# 04b3_BATT_CHARGER.net
KiCad netlist of a schematic drawn in Altium Designer
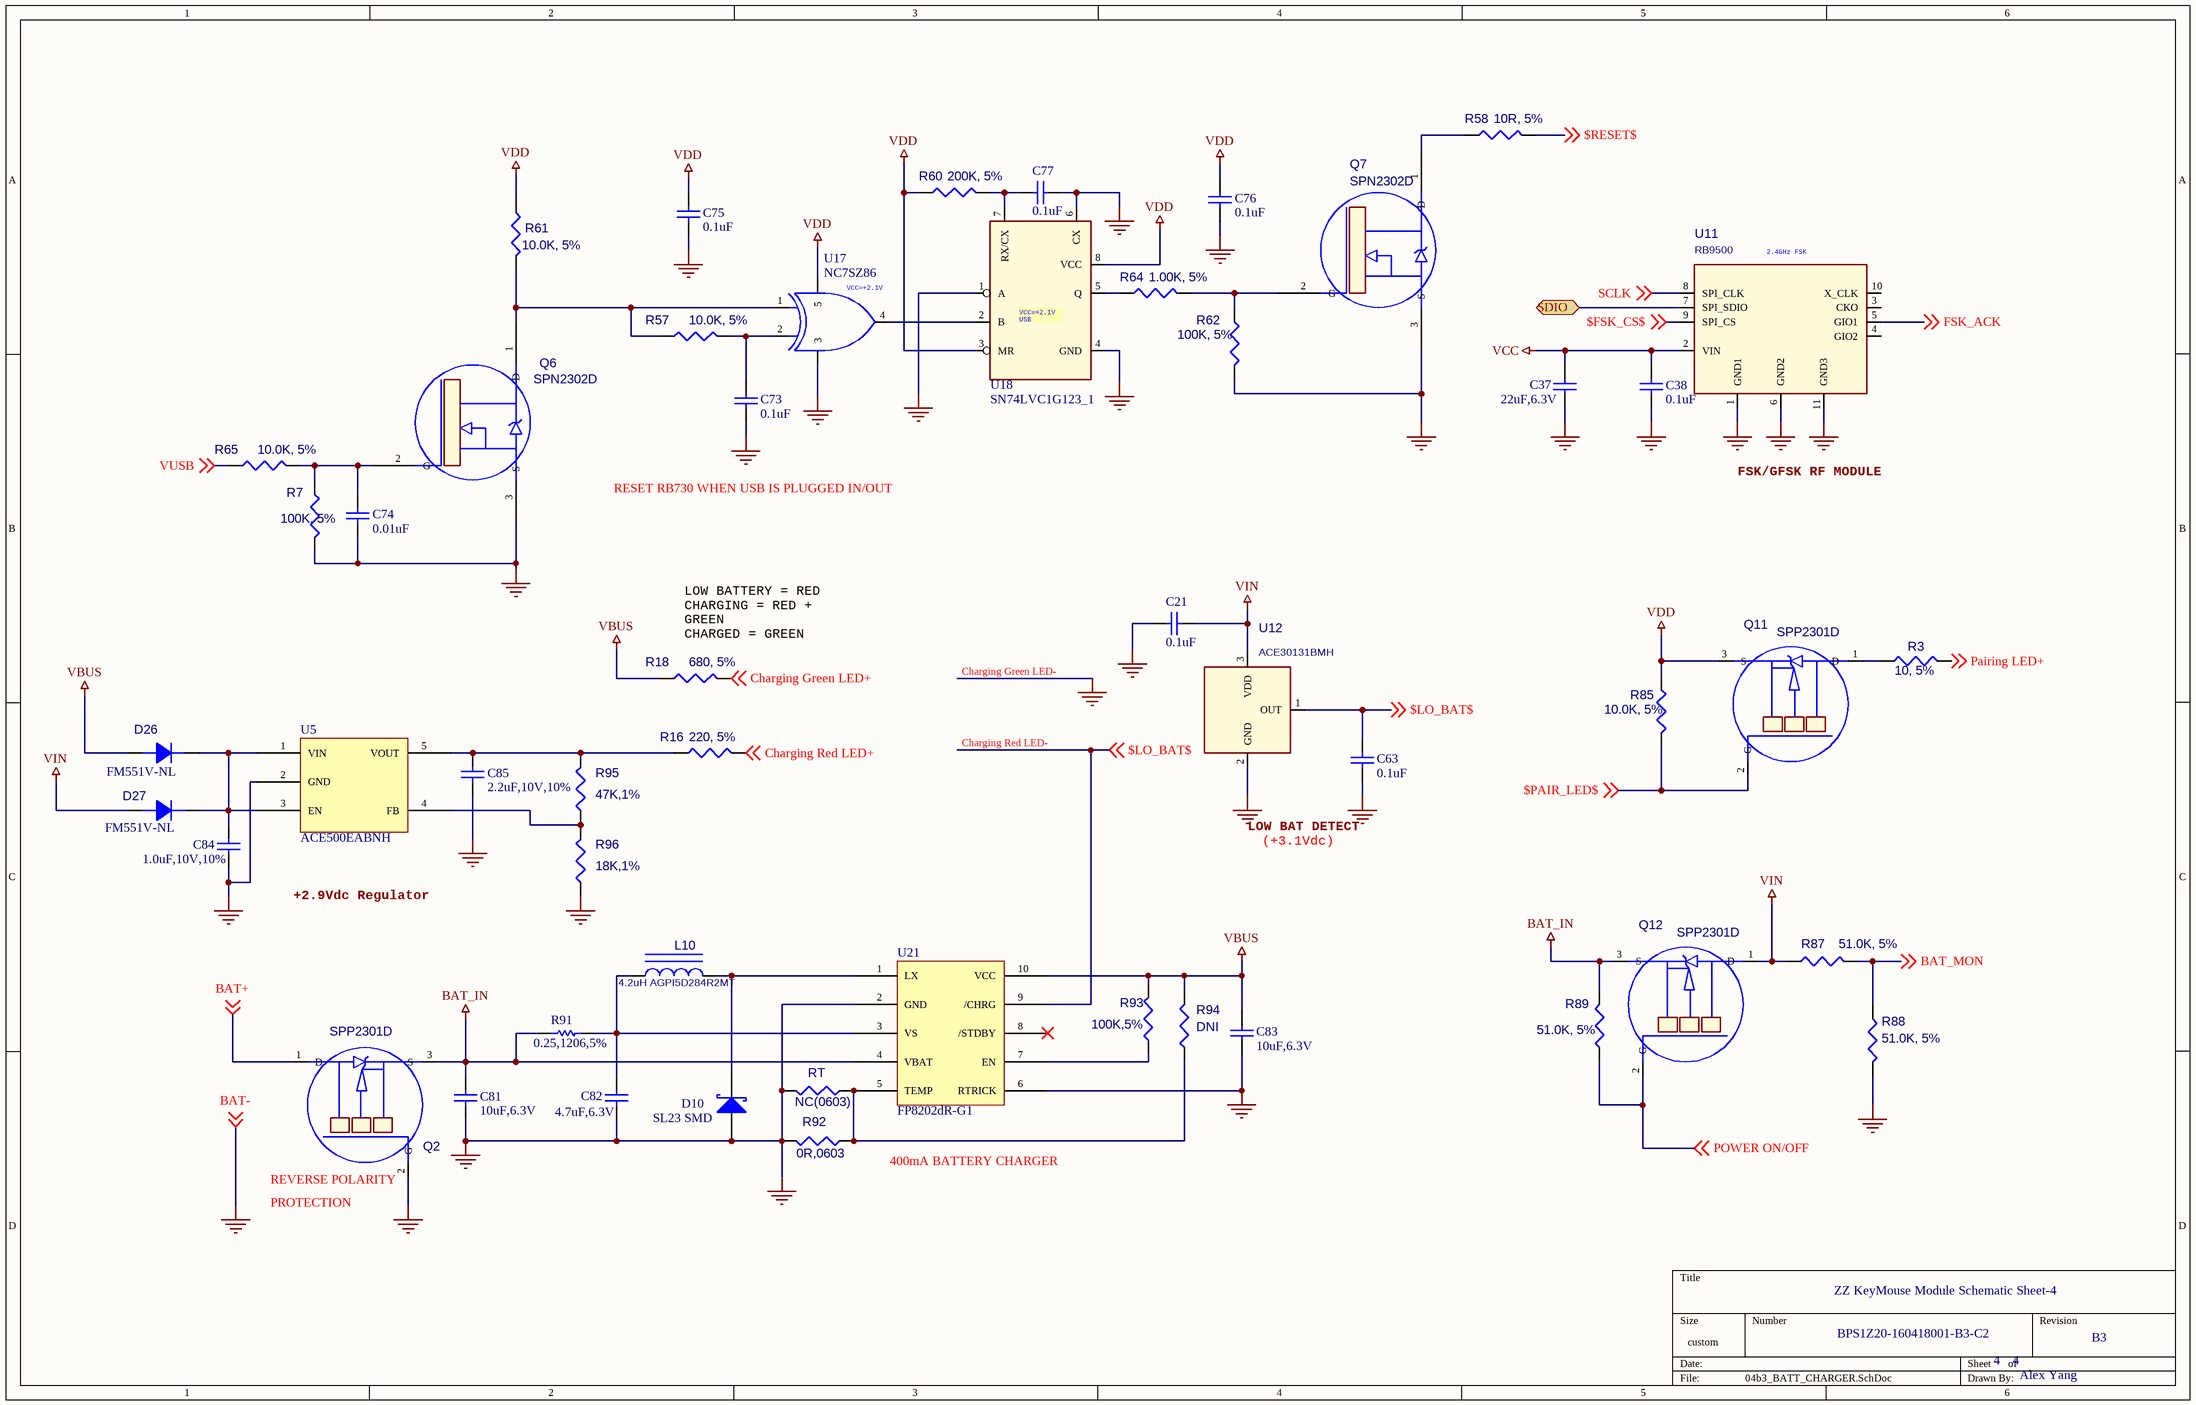
[diagram p0: 04b3_BATT_CHARGER.SchDoc]

(export (version "E")
  (design (tool "Eeschema 10.0.6"))
  (components
    (comp (ref "C21")
      (value "0.1uF")
      (footprint "0603")
      (description "Capacitor")
      (libsource (lib "Miscellaneous Devices") (part "Cap"))
    )
    (comp (ref "C37")
      (value "22uF,6.3V")
      (footprint "MIN0805")
      (description "Capacitor")
      (libsource (lib "Miscellaneous Devices") (part "Cap"))
    )
    (comp (ref "C38")
      (value "0.1uF")
      (footprint "0603")
      (description "Capacitor")
      (libsource (lib "Miscellaneous Devices") (part "Cap"))
    )
    (comp (ref "C63")
      (value "0.1uF")
      (footprint "0603")
      (description "Capacitor")
      (libsource (lib "Miscellaneous Devices") (part "Cap"))
    )
    (comp (ref "C73")
      (value "0.1uF")
      (footprint "0603")
      (description "Capacitor")
      (libsource (lib "Miscellaneous Devices") (part "Cap"))
    )
    (comp (ref "C74")
      (value "0.01uF")
      (footprint "0603")
      (description "Capacitor")
      (libsource (lib "Miscellaneous Devices") (part "Cap"))
    )
    (comp (ref "C75")
      (value "0.1uF")
      (footprint "0603")
      (description "Capacitor")
      (libsource (lib "Miscellaneous Devices") (part "Cap"))
    )
    (comp (ref "C76")
      (value "0.1uF")
      (footprint "0603")
      (description "Capacitor")
      (libsource (lib "Miscellaneous Devices") (part "Cap"))
    )
    (comp (ref "C77")
      (value "0.1uF")
      (footprint "0603")
      (description "Capacitor")
      (libsource (lib "Miscellaneous Devices") (part "Cap"))
    )
    (comp (ref "C81")
      (value "10uF,6.3V")
      (footprint "0603")
      (description "Capacitor")
      (libsource (lib "Miscellaneous Devices") (part "Cap"))
    )
    (comp (ref "C82")
      (value "4.7uF,6.3V")
      (footprint "0603")
      (description "Capacitor")
      (libsource (lib "Miscellaneous Devices") (part "Cap"))
    )
    (comp (ref "C83")
      (value "10uF,6.3V")
      (footprint "0603")
      (description "Capacitor")
      (libsource (lib "Miscellaneous Devices") (part "Cap"))
    )
    (comp (ref "C84")
      (value "1.0uF,10V,10%")
      (footprint "0603")
      (description "Capacitor")
      (libsource (lib "Miscellaneous Devices") (part "Cap"))
    )
    (comp (ref "C85")
      (value "2.2uF,10V,10%")
      (footprint "0603")
      (description "Capacitor")
      (libsource (lib "Miscellaneous Devices") (part "Cap"))
    )
    (comp (ref "D10")
      (value "SL23 SMD")
      (footprint "Sl23")
      (description "Silicon RF Schottky")
      (fields (field (name "PUBLISHER") "Altium Limited"))
      (libsource (lib "Miscellaneous Devices") (part "Diode BAT17"))
    )
    (comp (ref "D26")
      (value "DIODE")
      (footprint "FM551-NL-2")
      (fields (field (name "ALTIUM_UNNAMED_1") "FM551V-NL"))
      (libsource (lib "L MAIN_Library") (part "DIODE"))
    )
    (comp (ref "D27")
      (value "DIODE")
      (footprint "FM551-NL-2")
      (fields (field (name "ALTIUM_UNNAMED_1") "FM551V-NL"))
      (libsource (lib "L MAIN_Library") (part "DIODE"))
    )
    (comp (ref "L10")
      (value "4.2uH AGPI5D284R2MT")
      (footprint "AGPI15D284R2MT")
      (libsource (lib "*") (part "INDUCTOR IRON"))
    )
    (comp (ref "Q2") (value "SPP2301D") (footprint "SOT23") (libsource (lib "") (part "AO3435_1")))
    (comp (ref "Q6") (value "SPN2302D") (footprint "SOT23") (libsource (lib "L MAIN") (part "AO3416")))
    (comp (ref "Q7") (value "SPN2302D") (footprint "SOT23") (libsource (lib "L MAIN") (part "AO3416")))
    (comp (ref "Q11") (value "SPP2301D") (footprint "SOT23") (libsource (lib "R MAIN") (part "AO3435")))
    (comp (ref "Q12") (value "SPP2301D") (footprint "SOT23") (libsource (lib "R MAIN") (part "AO3435")))
    (comp (ref "R3") (value "10, 5%") (footprint "0402") (libsource (lib "*") (part "R")))
    (comp (ref "R7") (value "100K, 5%") (footprint "0402") (libsource (lib "*") (part "R")))
    (comp (ref "R16") (value "220, 5%") (footprint "0402") (libsource (lib "*") (part "R")))
    (comp (ref "R18") (value "680, 5%") (footprint "0402") (libsource (lib "*") (part "R")))
    (comp (ref "R57") (value "10.0K, 5%") (footprint "0402") (libsource (lib "*") (part "R")))
    (comp (ref "R58") (value "10R, 5%") (footprint "0402") (libsource (lib "*") (part "R")))
    (comp (ref "R60") (value "200K, 5%") (footprint "0402") (libsource (lib "*") (part "R")))
    (comp (ref "R61") (value "10.0K, 5%") (footprint "0402") (libsource (lib "*") (part "R")))
    (comp (ref "R62") (value "100K, 5%") (footprint "0402") (libsource (lib "*") (part "R")))
    (comp (ref "R64") (value "1.00K, 5%") (footprint "0402") (libsource (lib "*") (part "R")))
    (comp (ref "R65") (value "10.0K, 5%") (footprint "0402") (libsource (lib "*") (part "R")))
    (comp (ref "R85") (value "10.0K, 5%") (footprint "0402") (libsource (lib "*") (part "R")))
    (comp (ref "R87") (value "51.0K, 5%") (footprint "0402") (libsource (lib "*") (part "R")))
    (comp (ref "R88") (value "51.0K, 5%") (footprint "0402") (libsource (lib "*") (part "R")))
    (comp (ref "R89") (value "51.0K, 5%") (footprint "0402") (libsource (lib "*") (part "R")))
    (comp (ref "R91")
      (value "0.25,1206,5%")
      (footprint "1206")
      (description "Resistor")
      (fields (field (name "PUBLISHER") "Altium Limited"))
      (libsource (lib "Miscellaneous Devices") (part "Res1"))
    )
    (comp (ref "R92") (value "0R,0603") (footprint "0603") (libsource (lib "*") (part "R")))
    (comp (ref "R93") (value "100K,5%") (footprint "0402") (libsource (lib "*") (part "R")))
    (comp (ref "R94") (value "DNI") (footprint "0402") (libsource (lib "*") (part "R")))
    (comp (ref "R95") (value "47K,1%") (footprint "0402") (libsource (lib "*") (part "R")))
    (comp (ref "R96") (value "18K,1%") (footprint "0402") (libsource (lib "*") (part "R")))
    (comp (ref "RT") (value "NC(0603)") (footprint "0603") (libsource (lib "*") (part "R")))
    (comp (ref "U5")
      (value "ACE500EABNH")
      (footprint "SOT23-5")
      (fields (field (name "PUBLISHER") "Altium Limited"))
      (libsource (lib "ZZ KeyMouse Module") (part "ACE500EABNH"))
    )
    (comp (ref "U11") (value "RB9500") (footprint "RB9500_MODULE_SMT") (libsource (lib "*") (part "RB9500")))
    (comp (ref "U12") (value "ACE30131BMH") (footprint "SOT23") (libsource (lib "*") (part "STM1061N31WX6F")))
    (comp (ref "U17")
      (value "NC7SZ86")
      (footprint "SC70-5")
      (libsource (lib "L MAIN_Library") (part "NC7SZ86"))
    )
    (comp (ref "U18")
      (value "SN74LVC1G123_1")
      (footprint "US8_ON_SEMI_2MMX2.3MM")
      (libsource (lib "L MAIN_Library") (part "SN74LVC1G123_1"))
    )
    (comp (ref "U21")
      (value "FP8202dR-G1")
      (footprint "DFN10")
      (fields (field (name "PUBLISHER") "Altium Limited"))
      (libsource (lib "ZZ KeyMouse Module") (part "FP8202dR-G1"))
    )
  )
  (nets
    (net (code "1") (name "$FSK_CS$") (class "Default")
      (node (ref "U11") (pin "9") (pinfunction "SPI_CS_9") (pintype "passive"))
    )
    (net (code "2") (name "$LO_BAT$") (class "Default")
      (node (ref "C63") (pin "2") (pinfunction "2_2") (pintype "passive"))
      (node (ref "U12") (pin "1") (pinfunction "OUT_1") (pintype "passive"))
      (node (ref "U21") (pin "9") (pinfunction "/CHRG_9") (pintype "passive"))
    )
    (net (code "3") (name "$PAIR_LED$") (class "Default")
      (node (ref "Q11") (pin "2") (pinfunction "G_2") (pintype "passive"))
      (node (ref "R85") (pin "2") (pinfunction "2_2") (pintype "passive"))
    )
    (net (code "4") (name "$RESET$") (class "Default")
      (node (ref "R58") (pin "2") (pinfunction "2_2") (pintype "passive"))
    )
    (net (code "5") (name "/SDIO") (class "Default")
      (node (ref "U11") (pin "7") (pinfunction "SPI_SDIO_7") (pintype "passive"))
    )
    (net (code "6") (name "BAT+") (class "Default")
      (node (ref "Q2") (pin "1") (pinfunction "D_1") (pintype "passive"))
    )
    (net (code "7") (name "BAT-") (class "Default")
      (node (ref "C21") (pin "2") (pinfunction "2_2") (pintype "passive"))
      (node (ref "C37") (pin "1") (pinfunction "1_1") (pintype "passive"))
      (node (ref "C38") (pin "1") (pinfunction "1_1") (pintype "passive"))
      (node (ref "C63") (pin "1") (pinfunction "1_1") (pintype "passive"))
      (node (ref "C73") (pin "1") (pinfunction "1_1") (pintype "passive"))
      (node (ref "C74") (pin "1") (pinfunction "1_1") (pintype "passive"))
      (node (ref "C75") (pin "1") (pinfunction "1_1") (pintype "passive"))
      (node (ref "C76") (pin "1") (pinfunction "1_1") (pintype "passive"))
      (node (ref "C77") (pin "1") (pinfunction "1_1") (pintype "passive"))
      (node (ref "C81") (pin "1") (pinfunction "1_1") (pintype "passive"))
      (node (ref "C82") (pin "1") (pinfunction "1_1") (pintype "passive"))
      (node (ref "C83") (pin "1") (pinfunction "1_1") (pintype "passive"))
      (node (ref "C84") (pin "1") (pinfunction "1_1") (pintype "passive"))
      (node (ref "C85") (pin "1") (pinfunction "1_1") (pintype "passive"))
      (node (ref "D10") (pin "1") (pinfunction "A_1") (pintype "passive"))
      (node (ref "Q2") (pin "2") (pinfunction "G_2") (pintype "passive"))
      (node (ref "Q6") (pin "3") (pinfunction "S_3") (pintype "passive"))
      (node (ref "Q7") (pin "3") (pinfunction "S_3") (pintype "passive"))
      (node (ref "R62") (pin "1") (pinfunction "1_1") (pintype "passive"))
      (node (ref "R7") (pin "1") (pinfunction "1_1") (pintype "passive"))
      (node (ref "R88") (pin "2") (pinfunction "2_2") (pintype "passive"))
      (node (ref "R92") (pin "1") (pinfunction "1_1") (pintype "passive"))
      (node (ref "R96") (pin "2") (pinfunction "2_2") (pintype "passive"))
      (node (ref "RT") (pin "1") (pinfunction "1_1") (pintype "passive"))
      (node (ref "U11") (pin "1") (pinfunction "GND1_1") (pintype "passive"))
      (node (ref "U11") (pin "11") (pinfunction "GND3_11") (pintype "passive"))
      (node (ref "U11") (pin "6") (pinfunction "GND2_6") (pintype "passive"))
      (node (ref "U12") (pin "2") (pinfunction "GND_2") (pintype "passive"))
      (node (ref "U17") (pin "3") (pinfunction "3_3") (pintype "power_in"))
      (node (ref "U18") (pin "1") (pinfunction "A_1") (pintype "passive"))
      (node (ref "U18") (pin "4") (pinfunction "GND_4") (pintype "power_in"))
      (node (ref "U18") (pin "6") (pinfunction "CX_6") (pintype "passive"))
      (node (ref "U21") (pin "2") (pinfunction "GND_2") (pintype "passive"))
      (node (ref "U21") (pin "6") (pinfunction "RTRICK_6") (pintype "passive"))
      (node (ref "U5") (pin "2") (pinfunction "GND_2") (pintype "passive"))
    )
    (net (code "8") (name "BAT_IN") (class "Default")
      (node (ref "C81") (pin "2") (pinfunction "2_2") (pintype "passive"))
      (node (ref "Q12") (pin "3") (pinfunction "S_3") (pintype "passive"))
      (node (ref "Q2") (pin "3") (pinfunction "S_3") (pintype "passive"))
      (node (ref "R89") (pin "1") (pinfunction "1_1") (pintype "passive"))
      (node (ref "R91") (pin "1") (pinfunction "1_1") (pintype "passive"))
      (node (ref "U21") (pin "4") (pinfunction "VBAT_4") (pintype "passive"))
    )
    (net (code "9") (name "BAT_MON") (class "Default")
      (node (ref "R87") (pin "2") (pinfunction "2_2") (pintype "passive"))
      (node (ref "R88") (pin "1") (pinfunction "1_1") (pintype "passive"))
    )
    (net (code "10") (name "Charging Green LED+") (class "Default")
      (node (ref "R18") (pin "2") (pinfunction "2_2") (pintype "passive"))
    )
    (net (code "11") (name "Charging Red LED+") (class "Default")
      (node (ref "R16") (pin "2") (pinfunction "2_2") (pintype "passive"))
    )
    (net (code "12") (name "FSK_ACK") (class "Default")
      (node (ref "U11") (pin "5") (pinfunction "GIO1_5") (pintype "passive"))
    )
    (net (code "13") (name "Net-(C73-Pad2)") (class "Default")
      (node (ref "C73") (pin "2") (pinfunction "2_2") (pintype "passive"))
      (node (ref "R57") (pin "2") (pinfunction "2_2") (pintype "passive"))
      (node (ref "U17") (pin "2") (pinfunction "2_2") (pintype "passive"))
    )
    (net (code "14") (name "Net-(D10-K)") (class "Default")
      (node (ref "D10") (pin "2") (pinfunction "K_2") (pintype "passive"))
      (node (ref "L10") (pin "2") (pinfunction "2_2") (pintype "passive"))
      (node (ref "U21") (pin "1") (pinfunction "LX_1") (pintype "passive"))
    )
    (net (code "15") (name "Net-(Q6-D)") (class "Default")
      (node (ref "Q6") (pin "1") (pinfunction "D_1") (pintype "passive"))
      (node (ref "R57") (pin "1") (pinfunction "1_1") (pintype "passive"))
      (node (ref "R61") (pin "2") (pinfunction "2_2") (pintype "passive"))
      (node (ref "U17") (pin "1") (pinfunction "1_1") (pintype "passive"))
    )
    (net (code "16") (name "Net-(Q6-G)") (class "Default")
      (node (ref "C74") (pin "2") (pinfunction "2_2") (pintype "passive"))
      (node (ref "Q6") (pin "2") (pinfunction "G_2") (pintype "passive"))
      (node (ref "R65") (pin "2") (pinfunction "2_2") (pintype "passive"))
      (node (ref "R7") (pin "2") (pinfunction "2_2") (pintype "passive"))
    )
    (net (code "17") (name "Net-(Q7-D)") (class "Default")
      (node (ref "Q7") (pin "1") (pinfunction "D_1") (pintype "passive"))
      (node (ref "R58") (pin "1") (pinfunction "1_1") (pintype "passive"))
    )
    (net (code "18") (name "Net-(Q7-G)") (class "Default")
      (node (ref "Q7") (pin "2") (pinfunction "G_2") (pintype "passive"))
      (node (ref "R62") (pin "2") (pinfunction "2_2") (pintype "passive"))
      (node (ref "R64") (pin "2") (pinfunction "2_2") (pintype "passive"))
    )
    (net (code "19") (name "Net-(Q11-D)") (class "Default")
      (node (ref "Q11") (pin "1") (pinfunction "D_1") (pintype "passive"))
      (node (ref "R3") (pin "1") (pinfunction "1_1") (pintype "passive"))
    )
    (net (code "20") (name "Net-(U5-EN)") (class "Default")
      (node (ref "C84") (pin "2") (pinfunction "2_2") (pintype "passive"))
      (node (ref "D26") (pin "K") (pinfunction "K_K") (pintype "passive"))
      (node (ref "D27") (pin "K") (pinfunction "K_K") (pintype "passive"))
      (node (ref "U5") (pin "1") (pinfunction "VIN_1") (pintype "passive"))
      (node (ref "U5") (pin "3") (pinfunction "EN_3") (pintype "passive"))
    )
    (net (code "21") (name "Net-(U5-FB)") (class "Default")
      (node (ref "R95") (pin "2") (pinfunction "2_2") (pintype "passive"))
      (node (ref "R96") (pin "1") (pinfunction "1_1") (pintype "passive"))
      (node (ref "U5") (pin "4") (pinfunction "FB_4") (pintype "passive"))
    )
    (net (code "22") (name "Net-(U5-VOUT)") (class "Default")
      (node (ref "C85") (pin "2") (pinfunction "2_2") (pintype "passive"))
      (node (ref "R16") (pin "1") (pinfunction "1_1") (pintype "passive"))
      (node (ref "R95") (pin "1") (pinfunction "1_1") (pintype "passive"))
      (node (ref "U5") (pin "5") (pinfunction "VOUT_5") (pintype "passive"))
    )
    (net (code "23") (name "Net-(U18-B)") (class "Default")
      (node (ref "U17") (pin "4") (pinfunction "4_4") (pintype "passive"))
      (node (ref "U18") (pin "2") (pinfunction "B_2") (pintype "passive"))
    )
    (net (code "24") (name "Net-(U18-Q)") (class "Default")
      (node (ref "R64") (pin "1") (pinfunction "1_1") (pintype "passive"))
      (node (ref "U18") (pin "5") (pinfunction "Q_5") (pintype "passive"))
    )
    (net (code "25") (name "Net-(U18-RX{slash}CX)") (class "Default")
      (node (ref "C77") (pin "2") (pinfunction "2_2") (pintype "passive"))
      (node (ref "R60") (pin "2") (pinfunction "2_2") (pintype "passive"))
      (node (ref "U18") (pin "7") (pinfunction "RX/CX_7") (pintype "passive"))
    )
    (net (code "26") (name "Net-(U21-EN)") (class "Default")
      (node (ref "R93") (pin "2") (pinfunction "2_2") (pintype "passive"))
      (node (ref "U21") (pin "7") (pinfunction "EN_7") (pintype "passive"))
    )
    (net (code "27") (name "Net-(U21-TEMP)") (class "Default")
      (node (ref "R92") (pin "2") (pinfunction "2_2") (pintype "passive"))
      (node (ref "R94") (pin "2") (pinfunction "2_2") (pintype "passive"))
      (node (ref "RT") (pin "2") (pinfunction "2_2") (pintype "passive"))
      (node (ref "U21") (pin "5") (pinfunction "TEMP_5") (pintype "passive"))
    )
    (net (code "28") (name "Net-(U21-VS)") (class "Default")
      (node (ref "C82") (pin "2") (pinfunction "2_2") (pintype "passive"))
      (node (ref "L10") (pin "1") (pinfunction "1_1") (pintype "passive"))
      (node (ref "R91") (pin "2") (pinfunction "2_2") (pintype "passive"))
      (node (ref "U21") (pin "3") (pinfunction "VS_3") (pintype "passive"))
    )
    (net (code "29") (name "POWER ON{slash}OFF") (class "Default")
      (node (ref "Q12") (pin "2") (pinfunction "G_2") (pintype "passive"))
      (node (ref "R89") (pin "2") (pinfunction "2_2") (pintype "passive"))
    )
    (net (code "30") (name "Pairing LED+") (class "Default")
      (node (ref "R3") (pin "2") (pinfunction "2_2") (pintype "passive"))
    )
    (net (code "31") (name "SCLK") (class "Default")
      (node (ref "U11") (pin "8") (pinfunction "SPI_CLK_8") (pintype "passive"))
    )
    (net (code "32") (name "VBUS") (class "Default")
      (node (ref "C83") (pin "2") (pinfunction "2_2") (pintype "passive"))
      (node (ref "D26") (pin "A") (pinfunction "A_A") (pintype "passive"))
      (node (ref "R18") (pin "1") (pinfunction "1_1") (pintype "passive"))
      (node (ref "R93") (pin "1") (pinfunction "1_1") (pintype "passive"))
      (node (ref "R94") (pin "1") (pinfunction "1_1") (pintype "passive"))
      (node (ref "U21") (pin "10") (pinfunction "VCC_10") (pintype "passive"))
    )
    (net (code "33") (name "VCC") (class "Default")
      (node (ref "C37") (pin "2") (pinfunction "2_2") (pintype "passive"))
      (node (ref "C38") (pin "2") (pinfunction "2_2") (pintype "passive"))
      (node (ref "U11") (pin "2") (pinfunction "VIN_2") (pintype "passive"))
    )
    (net (code "34") (name "VDD") (class "Default")
      (node (ref "C75") (pin "2") (pinfunction "2_2") (pintype "passive"))
      (node (ref "C76") (pin "2") (pinfunction "2_2") (pintype "passive"))
      (node (ref "Q11") (pin "3") (pinfunction "S_3") (pintype "passive"))
      (node (ref "R60") (pin "1") (pinfunction "1_1") (pintype "passive"))
      (node (ref "R61") (pin "1") (pinfunction "1_1") (pintype "passive"))
      (node (ref "R85") (pin "1") (pinfunction "1_1") (pintype "passive"))
      (node (ref "U17") (pin "5") (pinfunction "5_5") (pintype "power_in"))
      (node (ref "U18") (pin "3") (pinfunction "MR_3") (pintype "passive"))
      (node (ref "U18") (pin "8") (pinfunction "VCC_8") (pintype "power_in"))
    )
    (net (code "35") (name "VIN") (class "Default")
      (node (ref "C21") (pin "1") (pinfunction "1_1") (pintype "passive"))
      (node (ref "D27") (pin "A") (pinfunction "A_A") (pintype "passive"))
      (node (ref "Q12") (pin "1") (pinfunction "D_1") (pintype "passive"))
      (node (ref "R87") (pin "1") (pinfunction "1_1") (pintype "passive"))
      (node (ref "U12") (pin "3") (pinfunction "VDD_3") (pintype "passive"))
    )
    (net (code "36") (name "VUSB") (class "Default")
      (node (ref "R65") (pin "1") (pinfunction "1_1") (pintype "passive"))
    )
    (net (code "37") (name "unconnected-(U11-CKO-Pad3)") (class "Default")
      (node (ref "U11") (pin "3") (pinfunction "CKO_3") (pintype "passive"))
    )
    (net (code "38") (name "unconnected-(U11-GIO2-Pad4)") (class "Default")
      (node (ref "U11") (pin "4") (pinfunction "GIO2_4") (pintype "passive"))
    )
    (net (code "39") (name "unconnected-(U11-X_CLK-Pad10)") (class "Default")
      (node (ref "U11") (pin "10") (pinfunction "X_CLK_10") (pintype "passive"))
    )
    (net (code "40") (name "unconnected-(U21-{slash}STDBY-Pad8)") (class "Default")
      (node (ref "U21") (pin "8") (pinfunction "/STDBY_8") (pintype "passive+no_connect"))
    )
  )
)
